# V1_HUB.net
KiCad netlist of a schematic drawn in EAGLE
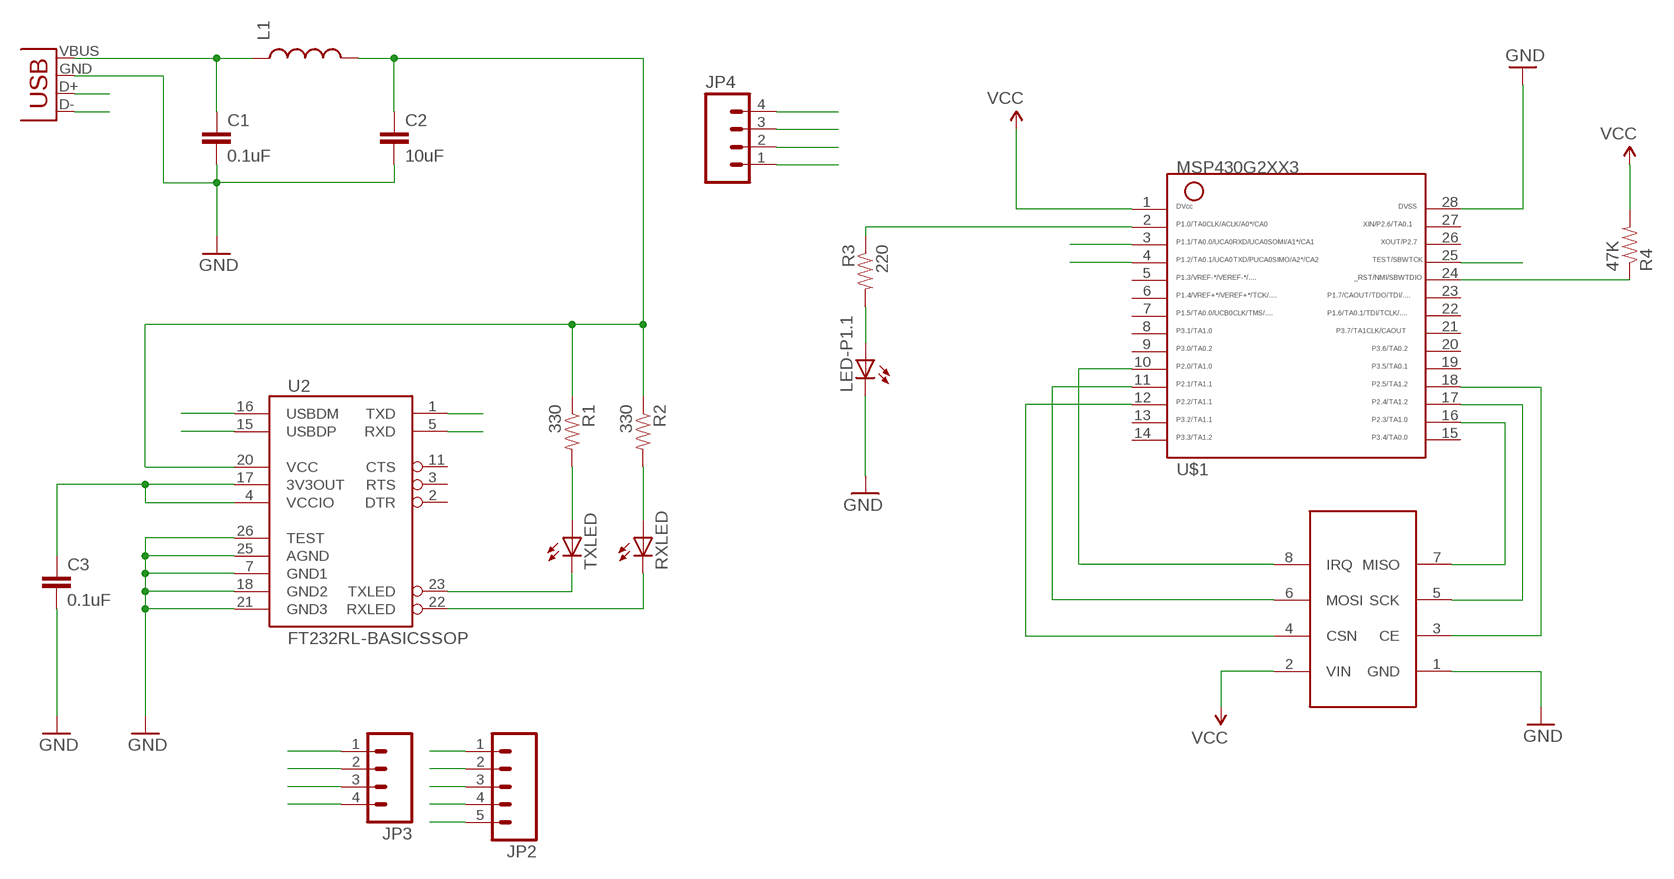
[diagram p0: schematic, sheet 1]

(export (version "E")
  (design (tool "Eeschema 10.0.6"))
  (components
    (comp (ref "C1")
      (value "0.1uF")
      (footprint "eagle-import:0805")
      (libsource (lib "eagle-import") (part "CAP0805"))
    )
    (comp (ref "C2")
      (value "10uF")
      (footprint "eagle-import:0805")
      (libsource (lib "eagle-import") (part "CAP0805"))
    )
    (comp (ref "C3")
      (value "0.1uF")
      (footprint "eagle-import:0805")
      (libsource (lib "eagle-import") (part "CAP0805"))
    )
    (comp (ref "JP1")
      (value "USB-B")
      (footprint "eagle-import:USB-A-H")
      (libsource (lib "eagle-import") (part "USB-A-H"))
    )
    (comp (ref "JP2")
      (value "M05LOCK")
      (footprint "eagle-import:1X05_LOCK")
      (libsource (lib "eagle-import") (part "M05LOCK"))
    )
    (comp (ref "JP3")
      (value "M04LOCK")
      (footprint "eagle-import:1X04_LOCK")
      (libsource (lib "eagle-import") (part "M04LOCK"))
    )
    (comp (ref "JP4")
      (value "M04LOCK")
      (footprint "eagle-import:1X04_LOCK")
      (libsource (lib "eagle-import") (part "M04LOCK"))
    )
    (comp (ref "L1")
      (value "INDUCTOR0805")
      (footprint "eagle-import:0805")
      (libsource (lib "eagle-import") (part "INDUCTOR0805"))
    )
    (comp (ref "LED-P1.1")
      (value "LED0805")
      (footprint "eagle-import:LED-0805")
      (libsource (lib "eagle-import") (part "LED0805"))
    )
    (comp (ref "R1")
      (value "330")
      (footprint "eagle-import:0805")
      (libsource (lib "eagle-import") (part "RESISTOR0805-RES"))
    )
    (comp (ref "R2")
      (value "330")
      (footprint "eagle-import:0805")
      (libsource (lib "eagle-import") (part "RESISTOR0805-RES"))
    )
    (comp (ref "R3")
      (value "220")
      (footprint "eagle-import:0805")
      (libsource (lib "eagle-import") (part "SparkFun-Resistors_RESISTOR0805-RES"))
    )
    (comp (ref "R4")
      (value "47K")
      (footprint "eagle-import:0805")
      (libsource (lib "eagle-import") (part "SparkFun-Resistors_RESISTOR0805-RES"))
    )
    (comp (ref "RXLED")
      (value "LED0805")
      (footprint "eagle-import:LED-0805")
      (libsource (lib "eagle-import") (part "LED0805"))
    )
    (comp (ref "TXLED")
      (value "LED0805")
      (footprint "eagle-import:LED-0805")
      (libsource (lib "eagle-import") (part "LED0805"))
    )
    (comp (ref "U$1")
      (value "MSP430G2553")
      (footprint "eagle-import:PW28")
      (libsource (lib "eagle-import") (part "G2XX3---PW28"))
    )
    (comp (ref "U1")
      (value "NRF24L01-4X2")
      (footprint "eagle-import:NRF24L01-4X2")
      (libsource (lib "eagle-import") (part "NRF24L01-4X2"))
    )
    (comp (ref "U2")
      (value "FT232RL-BASICSSOP")
      (footprint "eagle-import:SSOP28DB")
      (libsource (lib "eagle-import") (part "FT232RL-BASICSSOP"))
    )
  )
  (nets
    (net (code "1") (name "/5V") (class "Default")
      (node (ref "C2") (pin "1") (pinfunction "1_1") (pintype "passive"))
      (node (ref "JP2") (pin "5") (pinfunction "5_5") (pintype "passive"))
      (node (ref "L1") (pin "2") (pinfunction "2_2") (pintype "passive"))
      (node (ref "R1") (pin "1") (pinfunction "1_1") (pintype "passive"))
      (node (ref "R2") (pin "1") (pinfunction "1_1") (pintype "passive"))
      (node (ref "U2") (pin "20") (pinfunction "VCC_20") (pintype "power_in"))
    )
    (net (code "2") (name "/RESET") (class "Default")
      (node (ref "JP4") (pin "2") (pinfunction "2_2") (pintype "passive"))
      (node (ref "R4") (pin "1") (pinfunction "1_1") (pintype "passive"))
      (node (ref "U$1") (pin "24") (pinfunction "24_24") (pintype "bidirectional"))
    )
    (net (code "3") (name "/RX") (class "Default")
      (node (ref "JP2") (pin "3") (pinfunction "3_3") (pintype "passive"))
      (node (ref "JP3") (pin "3") (pinfunction "3_3") (pintype "passive"))
      (node (ref "U$1") (pin "4") (pinfunction "4_4") (pintype "bidirectional"))
      (node (ref "U2") (pin "5") (pinfunction "RXD_5") (pintype "input"))
    )
    (net (code "4") (name "/TEST") (class "Default")
      (node (ref "JP4") (pin "3") (pinfunction "3_3") (pintype "passive"))
      (node (ref "U$1") (pin "25") (pinfunction "25_25") (pintype "bidirectional"))
    )
    (net (code "5") (name "/TX") (class "Default")
      (node (ref "JP2") (pin "2") (pinfunction "2_2") (pintype "passive"))
      (node (ref "JP3") (pin "2") (pinfunction "2_2") (pintype "passive"))
      (node (ref "U$1") (pin "3") (pinfunction "3_3") (pintype "bidirectional"))
      (node (ref "U2") (pin "1") (pinfunction "TXD_1") (pintype "output"))
    )
    (net (code "6") (name "/USBDM") (class "Default")
      (node (ref "JP1") (pin "D-") (pinfunction "D+_D-") (pintype "bidirectional"))
      (node (ref "U2") (pin "16") (pinfunction "USBDM_16") (pintype "bidirectional"))
    )
    (net (code "7") (name "/USBDP") (class "Default")
      (node (ref "JP1") (pin "D+") (pinfunction "D-_D+") (pintype "bidirectional"))
      (node (ref "U2") (pin "15") (pinfunction "USBDP_15") (pintype "bidirectional"))
    )
    (net (code "8") (name "GND") (class "Default")
      (node (ref "C1") (pin "2") (pinfunction "2_2") (pintype "passive"))
      (node (ref "C2") (pin "2") (pinfunction "2_2") (pintype "passive"))
      (node (ref "C3") (pin "2") (pinfunction "2_2") (pintype "passive"))
      (node (ref "JP1") (pin "GND") (pinfunction "VBUS_GND") (pintype "bidirectional"))
      (node (ref "JP2") (pin "1") (pinfunction "1_1") (pintype "passive"))
      (node (ref "JP3") (pin "1") (pinfunction "1_1") (pintype "passive"))
      (node (ref "JP4") (pin "1") (pinfunction "1_1") (pintype "passive"))
      (node (ref "LED-P1.1") (pin "C") (pinfunction "C_C") (pintype "passive"))
      (node (ref "U$1") (pin "28") (pinfunction "28_28") (pintype "bidirectional"))
      (node (ref "U1") (pin "1") (pinfunction "GND_1") (pintype "power_in"))
      (node (ref "U2") (pin "18") (pinfunction "GND2_18") (pintype "power_in"))
      (node (ref "U2") (pin "21") (pinfunction "GND3_21") (pintype "power_in"))
      (node (ref "U2") (pin "25") (pinfunction "AGND_25") (pintype "power_in"))
      (node (ref "U2") (pin "26") (pinfunction "TEST_26") (pintype "input"))
      (node (ref "U2") (pin "7") (pinfunction "GND1_7") (pintype "power_in"))
    )
    (net (code "9") (name "Net-(JP1-GND)") (class "Default")
      (node (ref "C1") (pin "1") (pinfunction "1_1") (pintype "passive"))
      (node (ref "JP1") (pin "VBUS") (pinfunction "GND_VBUS") (pintype "bidirectional"))
      (node (ref "L1") (pin "1") (pinfunction "1_1") (pintype "passive"))
    )
    (net (code "10") (name "Net-(LED-P1.1-PadA)") (class "Default")
      (node (ref "LED-P1.1") (pin "A") (pinfunction "A_A") (pintype "passive"))
      (node (ref "R3") (pin "2") (pinfunction "2_2") (pintype "passive"))
    )
    (net (code "11") (name "Net-(R1-Pad2)") (class "Default")
      (node (ref "R1") (pin "2") (pinfunction "2_2") (pintype "passive"))
      (node (ref "TXLED") (pin "A") (pinfunction "A_A") (pintype "passive"))
    )
    (net (code "12") (name "Net-(R2-Pad2)") (class "Default")
      (node (ref "R2") (pin "2") (pinfunction "2_2") (pintype "passive"))
      (node (ref "RXLED") (pin "A") (pinfunction "A_A") (pintype "passive"))
    )
    (net (code "13") (name "Net-(R3-Pad1)") (class "Default")
      (node (ref "R3") (pin "1") (pinfunction "1_1") (pintype "passive"))
      (node (ref "U$1") (pin "2") (pinfunction "2_2") (pintype "bidirectional"))
    )
    (net (code "14") (name "Net-(U1-CE)") (class "Default")
      (node (ref "U$1") (pin "18") (pinfunction "18_18") (pintype "bidirectional"))
      (node (ref "U1") (pin "3") (pinfunction "CE_3") (pintype "input"))
    )
    (net (code "15") (name "Net-(U1-CSN)") (class "Default")
      (node (ref "U$1") (pin "12") (pinfunction "12_12") (pintype "bidirectional"))
      (node (ref "U1") (pin "4") (pinfunction "CSN_4") (pintype "input"))
    )
    (net (code "16") (name "Net-(U1-IRQ)") (class "Default")
      (node (ref "U$1") (pin "10") (pinfunction "10_10") (pintype "bidirectional"))
      (node (ref "U1") (pin "8") (pinfunction "IRQ_8") (pintype "output"))
    )
    (net (code "17") (name "Net-(U1-MISO)") (class "Default")
      (node (ref "U$1") (pin "16") (pinfunction "16_16") (pintype "bidirectional"))
      (node (ref "U1") (pin "7") (pinfunction "MISO_7") (pintype "output"))
    )
    (net (code "18") (name "Net-(U1-MOSI)") (class "Default")
      (node (ref "U$1") (pin "11") (pinfunction "11_11") (pintype "bidirectional"))
      (node (ref "U1") (pin "6") (pinfunction "MOSI_6") (pintype "input"))
    )
    (net (code "19") (name "Net-(U1-SCK)") (class "Default")
      (node (ref "U$1") (pin "17") (pinfunction "17_17") (pintype "bidirectional"))
      (node (ref "U1") (pin "5") (pinfunction "SCK_5") (pintype "input"))
    )
    (net (code "20") (name "Net-(U2-RXLED)") (class "Default")
      (node (ref "RXLED") (pin "C") (pinfunction "C_C") (pintype "passive"))
      (node (ref "U2") (pin "22") (pinfunction "RXLED_22") (pintype "bidirectional"))
    )
    (net (code "21") (name "Net-(U2-TXLED)") (class "Default")
      (node (ref "TXLED") (pin "C") (pinfunction "C_C") (pintype "passive"))
      (node (ref "U2") (pin "23") (pinfunction "TXLED_23") (pintype "bidirectional"))
    )
    (net (code "22") (name "VCC") (class "Default")
      (node (ref "C3") (pin "1") (pinfunction "1_1") (pintype "passive"))
      (node (ref "JP2") (pin "4") (pinfunction "4_4") (pintype "passive"))
      (node (ref "JP3") (pin "4") (pinfunction "4_4") (pintype "passive"))
      (node (ref "JP4") (pin "4") (pinfunction "4_4") (pintype "passive"))
      (node (ref "R4") (pin "2") (pinfunction "2_2") (pintype "passive"))
      (node (ref "U$1") (pin "1") (pinfunction "1_1") (pintype "bidirectional"))
      (node (ref "U1") (pin "2") (pinfunction "VIN_2") (pintype "power_in"))
      (node (ref "U2") (pin "17") (pinfunction "3V3OUT_17") (pintype "output"))
      (node (ref "U2") (pin "4") (pinfunction "VCCIO_4") (pintype "power_in"))
    )
    (net (code "23") (name "unconnected-(U$1-Pad5)") (class "Default")
      (node (ref "U$1") (pin "5") (pinfunction "5_5") (pintype "bidirectional"))
    )
    (net (code "24") (name "unconnected-(U$1-Pad6)") (class "Default")
      (node (ref "U$1") (pin "6") (pinfunction "6_6") (pintype "bidirectional"))
    )
    (net (code "25") (name "unconnected-(U$1-Pad7)") (class "Default")
      (node (ref "U$1") (pin "7") (pinfunction "7_7") (pintype "bidirectional"))
    )
    (net (code "26") (name "unconnected-(U$1-Pad8)") (class "Default")
      (node (ref "U$1") (pin "8") (pinfunction "8_8") (pintype "bidirectional"))
    )
    (net (code "27") (name "unconnected-(U$1-Pad9)") (class "Default")
      (node (ref "U$1") (pin "9") (pinfunction "9_9") (pintype "bidirectional"))
    )
    (net (code "28") (name "unconnected-(U$1-Pad13)") (class "Default")
      (node (ref "U$1") (pin "13") (pinfunction "13_13") (pintype "bidirectional"))
    )
    (net (code "29") (name "unconnected-(U$1-Pad14)") (class "Default")
      (node (ref "U$1") (pin "14") (pinfunction "14_14") (pintype "bidirectional"))
    )
    (net (code "30") (name "unconnected-(U$1-Pad15)") (class "Default")
      (node (ref "U$1") (pin "15") (pinfunction "15_15") (pintype "bidirectional"))
    )
    (net (code "31") (name "unconnected-(U$1-Pad19)") (class "Default")
      (node (ref "U$1") (pin "19") (pinfunction "19_19") (pintype "bidirectional"))
    )
    (net (code "32") (name "unconnected-(U$1-Pad20)") (class "Default")
      (node (ref "U$1") (pin "20") (pinfunction "20_20") (pintype "bidirectional"))
    )
    (net (code "33") (name "unconnected-(U$1-Pad21)") (class "Default")
      (node (ref "U$1") (pin "21") (pinfunction "21_21") (pintype "bidirectional"))
    )
    (net (code "34") (name "unconnected-(U$1-Pad22)") (class "Default")
      (node (ref "U$1") (pin "22") (pinfunction "22_22") (pintype "bidirectional"))
    )
    (net (code "35") (name "unconnected-(U$1-Pad23)") (class "Default")
      (node (ref "U$1") (pin "23") (pinfunction "23_23") (pintype "bidirectional"))
    )
    (net (code "36") (name "unconnected-(U$1-Pad26)") (class "Default")
      (node (ref "U$1") (pin "26") (pinfunction "26_26") (pintype "bidirectional"))
    )
    (net (code "37") (name "unconnected-(U$1-Pad27)") (class "Default")
      (node (ref "U$1") (pin "27") (pinfunction "27_27") (pintype "bidirectional"))
    )
    (net (code "38") (name "unconnected-(U2-CTS-Pad11)") (class "Default")
      (node (ref "U2") (pin "11") (pinfunction "CTS_11") (pintype "bidirectional"))
    )
    (net (code "39") (name "unconnected-(U2-DTR-Pad2)") (class "Default")
      (node (ref "U2") (pin "2") (pinfunction "DTR_2") (pintype "bidirectional"))
    )
    (net (code "40") (name "unconnected-(U2-RTS-Pad3)") (class "Default")
      (node (ref "U2") (pin "3") (pinfunction "RTS_3") (pintype "bidirectional"))
    )
  )
)
